# foldback.net
KiCad netlist of a schematic drawn in Altium Designer
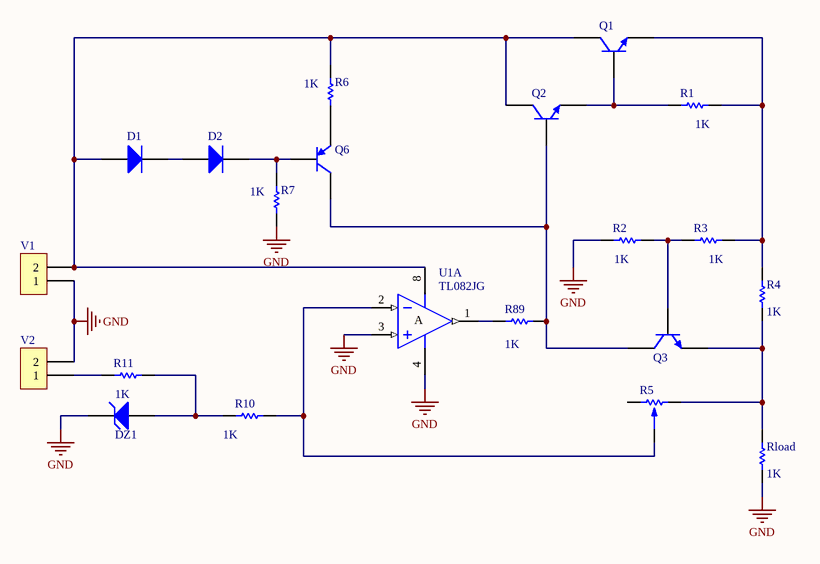
[diagram p0: foldback.SchDoc]

(export (version "E")
  (design (tool "Eeschema 10.0.6"))
  (components
    (comp (ref "D1")
      (value "Diode 1N914")
      (footprint "DO-35")
      (description "High Conductance Fast Diode")
      (fields (field (name "PUBLISHER") "Altium Limited"))
      (libsource (lib "Miscellaneous Devices") (part "Diode 1N914"))
    )
    (comp (ref "D2")
      (value "Diode 1N914")
      (footprint "DO-35")
      (description "High Conductance Fast Diode")
      (fields (field (name "PUBLISHER") "Altium Limited"))
      (libsource (lib "Miscellaneous Devices") (part "Diode 1N914"))
    )
    (comp (ref "DZ1")
      (value "D Zener")
      (footprint "DIODE-0.7")
      (description "Zener Diode")
      (fields (field (name "PUBLISHER") "Altium Limited"))
      (libsource (lib "Miscellaneous Devices") (part "D Zener"))
    )
    (comp (ref "Q1")
      (value "NPN")
      (footprint "TO-226-AA")
      (description "NPN Bipolar Transistor")
      (fields (field (name "PUBLISHER") "Altium Limited"))
      (libsource (lib "Miscellaneous Devices") (part "NPN"))
    )
    (comp (ref "Q2")
      (value "NPN")
      (footprint "TO-226-AA")
      (description "NPN Bipolar Transistor")
      (fields (field (name "PUBLISHER") "Altium Limited"))
      (libsource (lib "Miscellaneous Devices") (part "NPN"))
    )
    (comp (ref "Q3")
      (value "NPN")
      (footprint "TO-226-AA")
      (description "NPN Bipolar Transistor")
      (fields (field (name "PUBLISHER") "Altium Limited"))
      (libsource (lib "Miscellaneous Devices") (part "NPN"))
    )
    (comp (ref "Q6")
      (value "PNP")
      (footprint "SOT-23B_N")
      (description "PNP Bipolar Transistor")
      (fields (field (name "PUBLISHER") "Altium Limited"))
      (libsource (lib "Miscellaneous Devices") (part "PNP"))
    )
    (comp (ref "R1")
      (value "1K")
      (footprint "AXIAL-0.3")
      (description "Resistor")
      (fields (field (name "Comment") "Res1") (field (name "PUBLISHER") "Altium Limited"))
      (libsource (lib "Miscellaneous Devices") (part "Res1"))
    )
    (comp (ref "R2")
      (value "1K")
      (footprint "AXIAL-0.3")
      (description "Resistor")
      (fields (field (name "Comment") "Res1") (field (name "PUBLISHER") "Altium Limited"))
      (libsource (lib "Miscellaneous Devices") (part "Res1"))
    )
    (comp (ref "R3")
      (value "1K")
      (footprint "AXIAL-0.3")
      (description "Resistor")
      (fields (field (name "Comment") "Res1") (field (name "PUBLISHER") "Altium Limited"))
      (libsource (lib "Miscellaneous Devices") (part "Res1"))
    )
    (comp (ref "R4")
      (value "1K")
      (footprint "AXIAL-0.3")
      (description "Resistor")
      (fields (field (name "Comment") "Res1") (field (name "PUBLISHER") "Altium Limited"))
      (libsource (lib "Miscellaneous Devices") (part "Res1"))
    )
    (comp (ref "R5") (value "PRESET") (footprint "PRESET H") (libsource (lib "LIBEBAL") (part "PRESET")))
    (comp (ref "R6")
      (value "1K")
      (footprint "AXIAL-0.3")
      (description "Resistor")
      (fields (field (name "Comment") "Res1") (field (name "PUBLISHER") "Altium Limited"))
      (libsource (lib "Miscellaneous Devices") (part "Res1"))
    )
    (comp (ref "R7")
      (value "1K")
      (footprint "AXIAL-0.3")
      (description "Resistor")
      (fields (field (name "Comment") "Res1") (field (name "PUBLISHER") "Altium Limited"))
      (libsource (lib "Miscellaneous Devices") (part "Res1"))
    )
    (comp (ref "R10")
      (value "1K")
      (footprint "AXIAL-0.3")
      (description "Resistor")
      (fields (field (name "Comment") "Res1") (field (name "PUBLISHER") "Altium Limited"))
      (libsource (lib "Miscellaneous Devices") (part "Res1"))
    )
    (comp (ref "R11")
      (value "1K")
      (footprint "AXIAL-0.3")
      (description "Resistor")
      (fields (field (name "Comment") "Res1") (field (name "PUBLISHER") "Altium Limited"))
      (libsource (lib "Miscellaneous Devices") (part "Res1"))
    )
    (comp (ref "R89")
      (value "1K")
      (footprint "AXIAL-0.3")
      (description "Resistor")
      (fields (field (name "Comment") "Res1") (field (name "PUBLISHER") "Altium Limited"))
      (libsource (lib "Miscellaneous Devices") (part "Res1"))
    )
    (comp (ref "Rload")
      (value "1K")
      (footprint "AXIAL-0.3")
      (description "Resistor")
      (fields (field (name "Comment") "Res1") (field (name "PUBLISHER") "Altium Limited"))
      (libsource (lib "Miscellaneous Devices") (part "Res1"))
    )
    (comp (ref "U1")
      (value "TL082JG")
      (footprint "JG008")
      (description "JFET-Input Operational Amplifier")
      (fields (field (name "PUBLISHER") "Altium Limited"))
      (libsource (lib "TI Operational Amplifier") (part "TL082JG"))
    )
    (comp (ref "V1")
      (value "BORNERA 2")
      (footprint "BORNERA2")
      (libsource (lib "LIBEBAL") (part "BORNERA 2"))
    )
    (comp (ref "V2")
      (value "BORNERA 2")
      (footprint "BORNERA2")
      (libsource (lib "LIBEBAL") (part "BORNERA 2"))
    )
  )
  (nets
    (net (code "1") (name "GND") (class "Default")
      (node (ref "DZ1") (pin "2") (pinfunction "K_2") (pintype "passive"))
      (node (ref "R2") (pin "2") (pinfunction "2_2") (pintype "passive"))
      (node (ref "R7") (pin "1") (pinfunction "1_1") (pintype "passive"))
      (node (ref "Rload") (pin "1") (pinfunction "1_1") (pintype "passive"))
      (node (ref "U1") (pin "3") (pinfunction "IN+_3") (pintype "input"))
      (node (ref "U1") (pin "4") (pinfunction "V-_4") (pintype "power_in"))
      (node (ref "V1") (pin "1") (pinfunction "1_1") (pintype "passive"))
      (node (ref "V2") (pin "2") (pinfunction "2_2") (pintype "passive"))
    )
    (net (code "2") (name "Net-(D1-A)") (class "Default")
      (node (ref "D1") (pin "1") (pinfunction "A_1") (pintype "passive"))
      (node (ref "Q1") (pin "1") (pinfunction "C_1") (pintype "passive"))
      (node (ref "Q2") (pin "1") (pinfunction "C_1") (pintype "passive"))
      (node (ref "R6") (pin "2") (pinfunction "2_2") (pintype "passive"))
      (node (ref "U1") (pin "8") (pinfunction "V+_8") (pintype "power_in"))
      (node (ref "V1") (pin "2") (pinfunction "2_2") (pintype "passive"))
    )
    (net (code "3") (name "Net-(D1-K)") (class "Default")
      (node (ref "D1") (pin "2") (pinfunction "K_2") (pintype "passive"))
      (node (ref "D2") (pin "1") (pinfunction "A_1") (pintype "passive"))
    )
    (net (code "4") (name "Net-(D2-K)") (class "Default")
      (node (ref "D2") (pin "2") (pinfunction "K_2") (pintype "passive"))
      (node (ref "Q6") (pin "2") (pinfunction "B_2") (pintype "passive"))
      (node (ref "R7") (pin "2") (pinfunction "2_2") (pintype "passive"))
    )
    (net (code "5") (name "Net-(DZ1-A)") (class "Default")
      (node (ref "DZ1") (pin "1") (pinfunction "A_1") (pintype "passive"))
      (node (ref "R10") (pin "1") (pinfunction "1_1") (pintype "passive"))
      (node (ref "R11") (pin "2") (pinfunction "2_2") (pintype "passive"))
    )
    (net (code "6") (name "Net-(Q1-B)") (class "Default")
      (node (ref "Q1") (pin "2") (pinfunction "B_2") (pintype "passive"))
      (node (ref "Q2") (pin "3") (pinfunction "E_3") (pintype "passive"))
      (node (ref "R1") (pin "2") (pinfunction "2_2") (pintype "passive"))
    )
    (net (code "7") (name "Net-(Q1-E)") (class "Default")
      (node (ref "Q1") (pin "3") (pinfunction "E_3") (pintype "passive"))
      (node (ref "R1") (pin "1") (pinfunction "1_1") (pintype "passive"))
      (node (ref "R3") (pin "1") (pinfunction "1_1") (pintype "passive"))
      (node (ref "R4") (pin "1") (pinfunction "1_1") (pintype "passive"))
    )
    (net (code "8") (name "Net-(Q2-B)") (class "Default")
      (node (ref "Q2") (pin "2") (pinfunction "B_2") (pintype "passive"))
      (node (ref "Q3") (pin "1") (pinfunction "C_1") (pintype "passive"))
      (node (ref "Q6") (pin "1") (pinfunction "C_1") (pintype "passive"))
      (node (ref "R89") (pin "2") (pinfunction "2_2") (pintype "passive"))
    )
    (net (code "9") (name "Net-(Q3-B)") (class "Default")
      (node (ref "Q3") (pin "2") (pinfunction "B_2") (pintype "passive"))
      (node (ref "R2") (pin "1") (pinfunction "1_1") (pintype "passive"))
      (node (ref "R3") (pin "2") (pinfunction "2_2") (pintype "passive"))
    )
    (net (code "10") (name "Net-(Q3-E)") (class "Default")
      (node (ref "Q3") (pin "3") (pinfunction "E_3") (pintype "passive"))
      (node (ref "R4") (pin "2") (pinfunction "2_2") (pintype "passive"))
      (node (ref "R5") (pin "1") (pinfunction "1_1") (pintype "passive"))
      (node (ref "Rload") (pin "2") (pinfunction "2_2") (pintype "passive"))
    )
    (net (code "11") (name "Net-(Q6-E)") (class "Default")
      (node (ref "Q6") (pin "3") (pinfunction "E_3") (pintype "passive"))
      (node (ref "R6") (pin "1") (pinfunction "1_1") (pintype "passive"))
    )
    (net (code "12") (name "Net-(R11-Pad1)") (class "Default")
      (node (ref "R11") (pin "1") (pinfunction "1_1") (pintype "passive"))
      (node (ref "V2") (pin "1") (pinfunction "1_1") (pintype "passive"))
    )
    (net (code "13") (name "Net-(U1A-IN-)") (class "Default")
      (node (ref "R10") (pin "2") (pinfunction "2_2") (pintype "passive"))
      (node (ref "R5") (pin "2") (pinfunction "2_2") (pintype "passive"))
      (node (ref "U1") (pin "2") (pinfunction "IN-_2") (pintype "input"))
    )
    (net (code "14") (name "Net-(U1A-OUT)") (class "Default")
      (node (ref "R89") (pin "1") (pinfunction "1_1") (pintype "passive"))
      (node (ref "U1") (pin "1") (pinfunction "OUT_1") (pintype "output"))
    )
    (net (code "15") (name "unconnected-(R5-Pad3)") (class "Default")
      (node (ref "R5") (pin "3") (pinfunction "3_3") (pintype "passive"))
    )
  )
)
